# core4.net
KiCad netlist of a schematic drawn in EAGLE
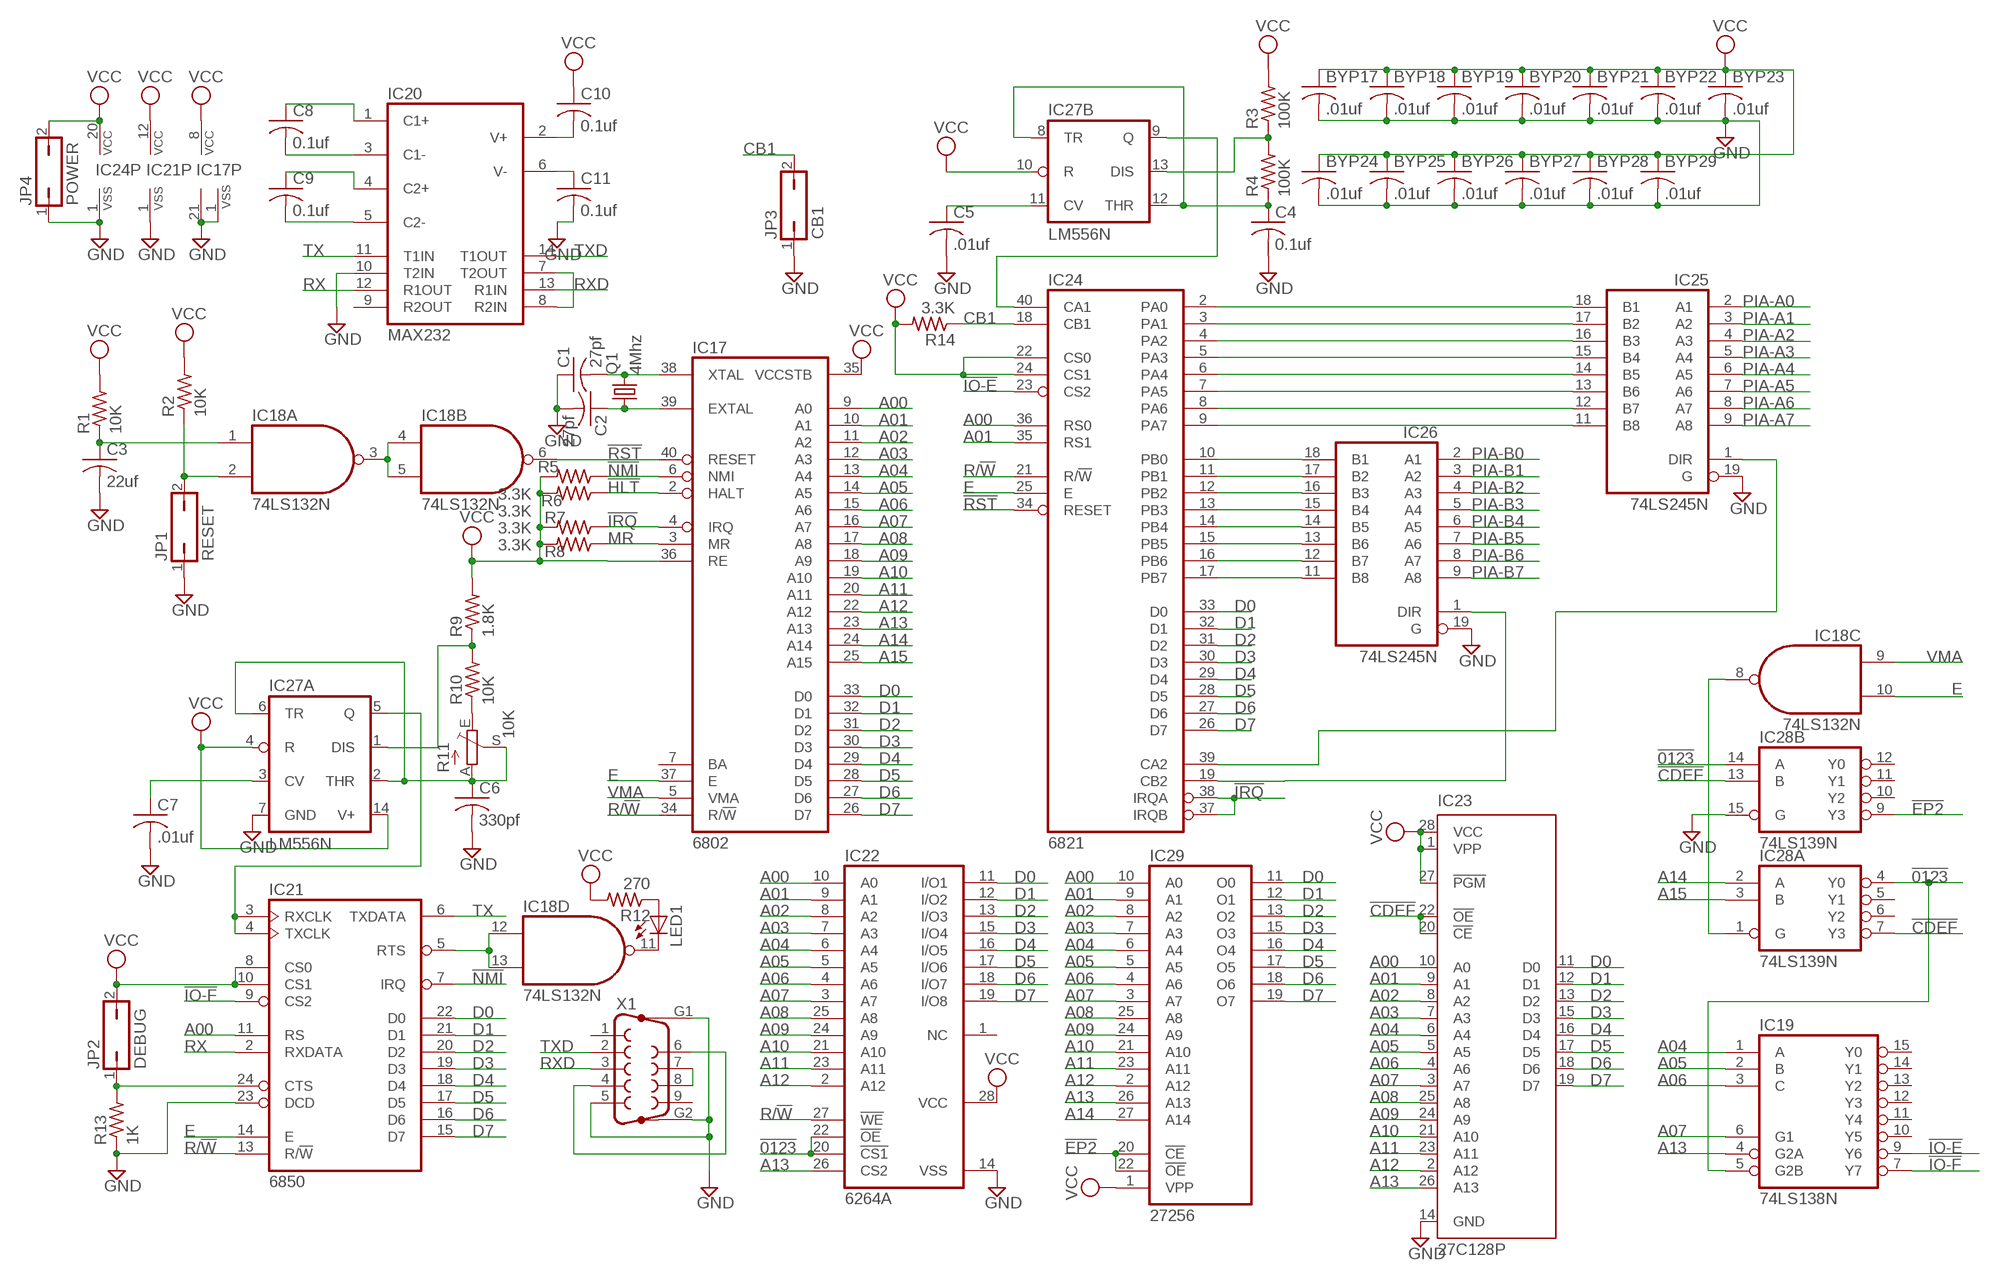
[diagram p0: schematic, sheet 1]
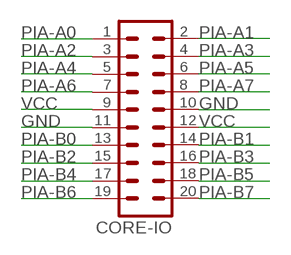
[diagram p1: schematic, sheet 2]

(export (version "E")
  (design (tool "Eeschema 10.0.6"))
  (components
    (comp (ref "CORE-IO")
      (value "MA10-2")
      (footprint "eagle-import:MA10-2")
      (libsource (lib "eagle-import") (part "MA10-2"))
    )
    (comp (ref "BYP17")
      (value ".01uf")
      (footprint "eagle-import:C050-025X075")
      (libsource (lib "eagle-import") (part "C-US050-025X075"))
    )
    (comp (ref "BYP18")
      (value ".01uf")
      (footprint "eagle-import:C050-025X075")
      (libsource (lib "eagle-import") (part "C-US050-025X075"))
    )
    (comp (ref "BYP19")
      (value ".01uf")
      (footprint "eagle-import:C050-025X075")
      (libsource (lib "eagle-import") (part "C-US050-025X075"))
    )
    (comp (ref "BYP20")
      (value ".01uf")
      (footprint "eagle-import:C050-025X075")
      (libsource (lib "eagle-import") (part "C-US050-025X075"))
    )
    (comp (ref "BYP21")
      (value ".01uf")
      (footprint "eagle-import:C050-025X075")
      (libsource (lib "eagle-import") (part "C-US050-025X075"))
    )
    (comp (ref "BYP22")
      (value ".01uf")
      (footprint "eagle-import:C050-025X075")
      (libsource (lib "eagle-import") (part "C-US050-025X075"))
    )
    (comp (ref "BYP23")
      (value ".01uf")
      (footprint "eagle-import:C050-025X075")
      (libsource (lib "eagle-import") (part "C-US050-025X075"))
    )
    (comp (ref "BYP24")
      (value ".01uf")
      (footprint "eagle-import:C050-025X075")
      (libsource (lib "eagle-import") (part "C-US050-025X075"))
    )
    (comp (ref "BYP25")
      (value ".01uf")
      (footprint "eagle-import:C050-025X075")
      (libsource (lib "eagle-import") (part "C-US050-025X075"))
    )
    (comp (ref "BYP26")
      (value ".01uf")
      (footprint "eagle-import:C050-025X075")
      (libsource (lib "eagle-import") (part "C-US050-025X075"))
    )
    (comp (ref "BYP27")
      (value ".01uf")
      (footprint "eagle-import:C050-025X075")
      (libsource (lib "eagle-import") (part "C-US050-025X075"))
    )
    (comp (ref "BYP28")
      (value ".01uf")
      (footprint "eagle-import:C050-025X075")
      (libsource (lib "eagle-import") (part "C-US050-025X075"))
    )
    (comp (ref "BYP29")
      (value ".01uf")
      (footprint "eagle-import:C050-025X075")
      (libsource (lib "eagle-import") (part "C-US050-025X075"))
    )
    (comp (ref "C1")
      (value "27pf")
      (footprint "eagle-import:C050-025X075")
      (libsource (lib "eagle-import") (part "C-US050-025X075"))
    )
    (comp (ref "C2")
      (value "27pf")
      (footprint "eagle-import:C050-025X075")
      (libsource (lib "eagle-import") (part "C-US050-025X075"))
    )
    (comp (ref "C3")
      (value "22uf")
      (footprint "eagle-import:C102-043X133")
      (libsource (lib "eagle-import") (part "C-US102-043X133"))
    )
    (comp (ref "C4")
      (value "0.1uf")
      (footprint "eagle-import:C050-025X075")
      (libsource (lib "eagle-import") (part "C-US050-025X075"))
    )
    (comp (ref "C5")
      (value ".01uf")
      (footprint "eagle-import:C050-025X075")
      (libsource (lib "eagle-import") (part "C-US050-025X075"))
    )
    (comp (ref "C6")
      (value "330pf")
      (footprint "eagle-import:C050-025X075")
      (libsource (lib "eagle-import") (part "C-US050-025X075"))
    )
    (comp (ref "C7")
      (value ".01uf")
      (footprint "eagle-import:C050-025X075")
      (libsource (lib "eagle-import") (part "C-US050-025X075"))
    )
    (comp (ref "C8")
      (value "0.1uf")
      (footprint "eagle-import:C050-025X075")
      (libsource (lib "eagle-import") (part "C-US050-025X075"))
    )
    (comp (ref "C9")
      (value "0.1uf")
      (footprint "eagle-import:C050-025X075")
      (libsource (lib "eagle-import") (part "C-US050-025X075"))
    )
    (comp (ref "C10")
      (value "0.1uf")
      (footprint "eagle-import:C050-025X075")
      (libsource (lib "eagle-import") (part "C-US050-025X075"))
    )
    (comp (ref "C11")
      (value "0.1uf")
      (footprint "eagle-import:C050-025X075")
      (libsource (lib "eagle-import") (part "C-US050-025X075"))
    )
    (comp (ref "IC17")
      (value "6802")
      (footprint "eagle-import:DIL40")
      (libsource (lib "eagle-import") (part "6802"))
    )
    (comp (ref "IC18")
      (value "74LS132N")
      (footprint "eagle-import:DIL14")
      (libsource (lib "eagle-import") (part "7400NLS"))
    )
    (comp (ref "IC19")
      (value "74LS138N")
      (footprint "eagle-import:DIL16")
      (libsource (lib "eagle-import") (part "74138NLS"))
    )
    (comp (ref "IC20")
      (value "MAX232")
      (footprint "eagle-import:DIL16")
      (fields (field (name "MF") "MAXIM") (field (name "MPN") "MAX232ACPE+"))
      (libsource (lib "eagle-import") (part "MAX232"))
    )
    (comp (ref "IC21")
      (value "6850")
      (footprint "eagle-import:DIL24")
      (fields (field (name "MF") "NTE ELECTRONICS") (field (name "MPN") "NTE6850"))
      (libsource (lib "eagle-import") (part "6850"))
    )
    (comp (ref "IC22")
      (value "6264A")
      (footprint "eagle-import:DIL28-6")
      (libsource (lib "eagle-import") (part "6264A"))
    )
    (comp (ref "IC23")
      (value "27C128P")
      (footprint "eagle-import:DIL28-6")
      (libsource (lib "eagle-import") (part "27128PC"))
    )
    (comp (ref "IC24")
      (value "6821")
      (footprint "eagle-import:DIL40")
      (fields (field (name "MF") "NTE ELECTRONICS") (field (name "MPN") "NTE6821"))
      (libsource (lib "eagle-import") (part "6821"))
    )
    (comp (ref "IC25")
      (value "74LS245N")
      (footprint "eagle-import:DIL20")
      (libsource (lib "eagle-import") (part "74245NLS"))
    )
    (comp (ref "IC26")
      (value "74LS245N")
      (footprint "eagle-import:DIL20")
      (libsource (lib "eagle-import") (part "74245NLS"))
    )
    (comp (ref "IC27")
      (value "LM556N")
      (footprint "eagle-import:DIL14")
      (libsource (lib "eagle-import") (part "556NLM"))
    )
    (comp (ref "IC28")
      (value "74LS139N")
      (footprint "eagle-import:DIL16")
      (libsource (lib "eagle-import") (part "74139NLS"))
    )
    (comp (ref "IC29")
      (value "27256")
      (footprint "eagle-import:DIL28")
      (libsource (lib "eagle-import") (part "27256"))
    )
    (comp (ref "JP1")
      (value "RESET")
      (footprint "eagle-import:JP1")
      (libsource (lib "eagle-import") (part "JP1Q"))
    )
    (comp (ref "JP2")
      (value "DEBUG")
      (footprint "eagle-import:JP1")
      (libsource (lib "eagle-import") (part "JP1Q"))
    )
    (comp (ref "JP3")
      (value "CB1")
      (footprint "eagle-import:JP1")
      (libsource (lib "eagle-import") (part "JP1Q"))
    )
    (comp (ref "JP4")
      (value "POWER")
      (footprint "eagle-import:JP1")
      (libsource (lib "eagle-import") (part "JP1Q"))
    )
    (comp (ref "LED1")
      (value "LED3MM")
      (footprint "eagle-import:LED3MM")
      (libsource (lib "eagle-import") (part "LED3MM"))
    )
    (comp (ref "Q1")
      (value "4Mhz")
      (footprint "eagle-import:HC18U-V")
      (libsource (lib "eagle-import") (part "CRYSTALHC18U-V"))
    )
    (comp (ref "R1")
      (value "10K")
      (footprint "eagle-import:0207_7")
      (libsource (lib "eagle-import") (part "R-US_0207/7"))
    )
    (comp (ref "R2")
      (value "10K")
      (footprint "eagle-import:0207_7")
      (libsource (lib "eagle-import") (part "R-US_0207/7"))
    )
    (comp (ref "R3")
      (value "100K")
      (footprint "eagle-import:0207_7")
      (libsource (lib "eagle-import") (part "R-US_0207/7"))
    )
    (comp (ref "R4")
      (value "100K")
      (footprint "eagle-import:0207_7")
      (libsource (lib "eagle-import") (part "R-US_0207/7"))
    )
    (comp (ref "R5")
      (value "3.3K")
      (footprint "eagle-import:0207_7")
      (libsource (lib "eagle-import") (part "R-US_0207/7"))
    )
    (comp (ref "R6")
      (value "3.3K")
      (footprint "eagle-import:0207_7")
      (libsource (lib "eagle-import") (part "R-US_0207/7"))
    )
    (comp (ref "R7")
      (value "3.3K")
      (footprint "eagle-import:0207_7")
      (libsource (lib "eagle-import") (part "R-US_0207/7"))
    )
    (comp (ref "R8")
      (value "3.3K")
      (footprint "eagle-import:0207_7")
      (libsource (lib "eagle-import") (part "R-US_0207/7"))
    )
    (comp (ref "R9")
      (value "1.8K")
      (footprint "eagle-import:0207_7")
      (libsource (lib "eagle-import") (part "R-US_0207/7"))
    )
    (comp (ref "R10")
      (value "10K")
      (footprint "eagle-import:0207_7")
      (libsource (lib "eagle-import") (part "R-US_0207/7"))
    )
    (comp (ref "R11")
      (value "10K")
      (footprint "eagle-import:SP19L")
      (libsource (lib "eagle-import") (part "TRIM_EU-B90P"))
    )
    (comp (ref "R12")
      (value "270")
      (footprint "eagle-import:0207_7")
      (libsource (lib "eagle-import") (part "R-US_0207/7"))
    )
    (comp (ref "R13")
      (value "1K")
      (footprint "eagle-import:0207_7")
      (libsource (lib "eagle-import") (part "R-US_0207/7"))
    )
    (comp (ref "R14")
      (value "3.3K")
      (footprint "eagle-import:0207_7")
      (libsource (lib "eagle-import") (part "R-US_0207/7"))
    )
    (comp (ref "X1")
      (value "F09HP")
      (footprint "eagle-import:F09HP")
      (libsource (lib "eagle-import") (part "F09HP"))
    )
  )
  (nets
    (net (code "1") (name "A00") (class "Default")
      (node (ref "IC17") (pin "9") (pinfunction "A0_9") (pintype "output"))
      (node (ref "IC21") (pin "11") (pinfunction "RS_11") (pintype "input"))
      (node (ref "IC22") (pin "10") (pinfunction "A0_10") (pintype "input"))
      (node (ref "IC23") (pin "10") (pinfunction "A0_10") (pintype "input"))
      (node (ref "IC24") (pin "36") (pinfunction "RS0_36") (pintype "input"))
      (node (ref "IC29") (pin "10") (pinfunction "A0_10") (pintype "input"))
    )
    (net (code "2") (name "A01") (class "Default")
      (node (ref "IC17") (pin "10") (pinfunction "A1_10") (pintype "output"))
      (node (ref "IC22") (pin "9") (pinfunction "A1_9") (pintype "input"))
      (node (ref "IC23") (pin "9") (pinfunction "A1_9") (pintype "input"))
      (node (ref "IC24") (pin "35") (pinfunction "RS1_35") (pintype "input"))
      (node (ref "IC29") (pin "9") (pinfunction "A1_9") (pintype "input"))
    )
    (net (code "3") (name "A02") (class "Default")
      (node (ref "IC17") (pin "11") (pinfunction "A2_11") (pintype "output"))
      (node (ref "IC22") (pin "8") (pinfunction "A2_8") (pintype "input"))
      (node (ref "IC23") (pin "8") (pinfunction "A2_8") (pintype "input"))
      (node (ref "IC29") (pin "8") (pinfunction "A2_8") (pintype "input"))
    )
    (net (code "4") (name "A03") (class "Default")
      (node (ref "IC17") (pin "12") (pinfunction "A3_12") (pintype "output"))
      (node (ref "IC22") (pin "7") (pinfunction "A3_7") (pintype "input"))
      (node (ref "IC23") (pin "7") (pinfunction "A3_7") (pintype "input"))
      (node (ref "IC29") (pin "7") (pinfunction "A3_7") (pintype "input"))
    )
    (net (code "5") (name "A04") (class "Default")
      (node (ref "IC17") (pin "13") (pinfunction "A4_13") (pintype "output"))
      (node (ref "IC19") (pin "1") (pinfunction "A_1") (pintype "input"))
      (node (ref "IC22") (pin "6") (pinfunction "A4_6") (pintype "input"))
      (node (ref "IC23") (pin "6") (pinfunction "A4_6") (pintype "input"))
      (node (ref "IC29") (pin "6") (pinfunction "A4_6") (pintype "input"))
    )
    (net (code "6") (name "A05") (class "Default")
      (node (ref "IC17") (pin "14") (pinfunction "A5_14") (pintype "output"))
      (node (ref "IC19") (pin "2") (pinfunction "B_2") (pintype "input"))
      (node (ref "IC22") (pin "5") (pinfunction "A5_5") (pintype "input"))
      (node (ref "IC23") (pin "5") (pinfunction "A5_5") (pintype "input"))
      (node (ref "IC29") (pin "5") (pinfunction "A5_5") (pintype "input"))
    )
    (net (code "7") (name "A06") (class "Default")
      (node (ref "IC17") (pin "15") (pinfunction "A6_15") (pintype "output"))
      (node (ref "IC19") (pin "3") (pinfunction "C_3") (pintype "input"))
      (node (ref "IC22") (pin "4") (pinfunction "A6_4") (pintype "input"))
      (node (ref "IC23") (pin "4") (pinfunction "A6_4") (pintype "input"))
      (node (ref "IC29") (pin "4") (pinfunction "A6_4") (pintype "input"))
    )
    (net (code "8") (name "A07") (class "Default")
      (node (ref "IC17") (pin "16") (pinfunction "A7_16") (pintype "output"))
      (node (ref "IC19") (pin "6") (pinfunction "G1_6") (pintype "input"))
      (node (ref "IC22") (pin "3") (pinfunction "A7_3") (pintype "input"))
      (node (ref "IC23") (pin "3") (pinfunction "A7_3") (pintype "input"))
      (node (ref "IC29") (pin "3") (pinfunction "A7_3") (pintype "input"))
    )
    (net (code "9") (name "A08") (class "Default")
      (node (ref "IC17") (pin "17") (pinfunction "A8_17") (pintype "output"))
      (node (ref "IC22") (pin "25") (pinfunction "A8_25") (pintype "input"))
      (node (ref "IC23") (pin "25") (pinfunction "A8_25") (pintype "input"))
      (node (ref "IC29") (pin "25") (pinfunction "A8_25") (pintype "input"))
    )
    (net (code "10") (name "A09") (class "Default")
      (node (ref "IC17") (pin "18") (pinfunction "A9_18") (pintype "output"))
      (node (ref "IC22") (pin "24") (pinfunction "A9_24") (pintype "input"))
      (node (ref "IC23") (pin "24") (pinfunction "A9_24") (pintype "input"))
      (node (ref "IC29") (pin "24") (pinfunction "A9_24") (pintype "input"))
    )
    (net (code "11") (name "A10") (class "Default")
      (node (ref "IC17") (pin "19") (pinfunction "A10_19") (pintype "output"))
      (node (ref "IC22") (pin "21") (pinfunction "A10_21") (pintype "input"))
      (node (ref "IC23") (pin "21") (pinfunction "A10_21") (pintype "input"))
      (node (ref "IC29") (pin "21") (pinfunction "A10_21") (pintype "input"))
    )
    (net (code "12") (name "A11") (class "Default")
      (node (ref "IC17") (pin "20") (pinfunction "A11_20") (pintype "output"))
      (node (ref "IC22") (pin "23") (pinfunction "A11_23") (pintype "input"))
      (node (ref "IC23") (pin "23") (pinfunction "A11_23") (pintype "input"))
      (node (ref "IC29") (pin "23") (pinfunction "A11_23") (pintype "input"))
    )
    (net (code "13") (name "A12") (class "Default")
      (node (ref "IC17") (pin "22") (pinfunction "A12_22") (pintype "output"))
      (node (ref "IC22") (pin "2") (pinfunction "A12_2") (pintype "input"))
      (node (ref "IC23") (pin "2") (pinfunction "A12_2") (pintype "input"))
      (node (ref "IC29") (pin "2") (pinfunction "A12_2") (pintype "input"))
    )
    (net (code "14") (name "A13") (class "Default")
      (node (ref "IC17") (pin "23") (pinfunction "A13_23") (pintype "output"))
      (node (ref "IC19") (pin "4") (pinfunction "G2A_4") (pintype "input"))
      (node (ref "IC22") (pin "26") (pinfunction "CS2_26") (pintype "input"))
      (node (ref "IC23") (pin "26") (pinfunction "A13_26") (pintype "input"))
      (node (ref "IC29") (pin "26") (pinfunction "A13_26") (pintype "input"))
    )
    (net (code "15") (name "A14") (class "Default")
      (node (ref "IC17") (pin "24") (pinfunction "A14_24") (pintype "output"))
      (node (ref "IC28") (pin "2") (pinfunction "A_2") (pintype "input"))
      (node (ref "IC29") (pin "27") (pinfunction "A14_27") (pintype "input"))
    )
    (net (code "16") (name "A15") (class "Default")
      (node (ref "IC17") (pin "25") (pinfunction "A15_25") (pintype "output"))
      (node (ref "IC28") (pin "3") (pinfunction "B_3") (pintype "input"))
    )
    (net (code "17") (name "CB1") (class "Default")
      (node (ref "IC24") (pin "18") (pinfunction "CB1_18") (pintype "input"))
      (node (ref "JP3") (pin "2") (pinfunction "2_2") (pintype "passive"))
      (node (ref "R14") (pin "1") (pinfunction "1_1") (pintype "passive"))
    )
    (net (code "18") (name "D0") (class "Default")
      (node (ref "IC17") (pin "33") (pinfunction "D0_33") (pintype "bidirectional"))
      (node (ref "IC21") (pin "22") (pinfunction "D0_22") (pintype "bidirectional"))
      (node (ref "IC22") (pin "11") (pinfunction "I/O1_11") (pintype "bidirectional"))
      (node (ref "IC23") (pin "11") (pinfunction "D0_11") (pintype "tri_state"))
      (node (ref "IC24") (pin "33") (pinfunction "D0_33") (pintype "bidirectional"))
      (node (ref "IC29") (pin "11") (pinfunction "O0_11") (pintype "tri_state"))
    )
    (net (code "19") (name "D1") (class "Default")
      (node (ref "IC17") (pin "32") (pinfunction "D1_32") (pintype "bidirectional"))
      (node (ref "IC21") (pin "21") (pinfunction "D1_21") (pintype "bidirectional"))
      (node (ref "IC22") (pin "12") (pinfunction "I/O2_12") (pintype "bidirectional"))
      (node (ref "IC23") (pin "12") (pinfunction "D1_12") (pintype "tri_state"))
      (node (ref "IC24") (pin "32") (pinfunction "D1_32") (pintype "bidirectional"))
      (node (ref "IC29") (pin "12") (pinfunction "O1_12") (pintype "tri_state"))
    )
    (net (code "20") (name "D2") (class "Default")
      (node (ref "IC17") (pin "31") (pinfunction "D2_31") (pintype "bidirectional"))
      (node (ref "IC21") (pin "20") (pinfunction "D2_20") (pintype "bidirectional"))
      (node (ref "IC22") (pin "13") (pinfunction "I/O3_13") (pintype "bidirectional"))
      (node (ref "IC23") (pin "13") (pinfunction "D2_13") (pintype "tri_state"))
      (node (ref "IC24") (pin "31") (pinfunction "D2_31") (pintype "bidirectional"))
      (node (ref "IC29") (pin "13") (pinfunction "O2_13") (pintype "tri_state"))
    )
    (net (code "21") (name "D3") (class "Default")
      (node (ref "IC17") (pin "30") (pinfunction "D3_30") (pintype "bidirectional"))
      (node (ref "IC21") (pin "19") (pinfunction "D3_19") (pintype "bidirectional"))
      (node (ref "IC22") (pin "15") (pinfunction "I/O4_15") (pintype "bidirectional"))
      (node (ref "IC23") (pin "15") (pinfunction "D3_15") (pintype "tri_state"))
      (node (ref "IC24") (pin "30") (pinfunction "D3_30") (pintype "bidirectional"))
      (node (ref "IC29") (pin "15") (pinfunction "O3_15") (pintype "tri_state"))
    )
    (net (code "22") (name "D4") (class "Default")
      (node (ref "IC17") (pin "29") (pinfunction "D4_29") (pintype "bidirectional"))
      (node (ref "IC21") (pin "18") (pinfunction "D4_18") (pintype "bidirectional"))
      (node (ref "IC22") (pin "16") (pinfunction "I/O5_16") (pintype "bidirectional"))
      (node (ref "IC23") (pin "16") (pinfunction "D4_16") (pintype "tri_state"))
      (node (ref "IC24") (pin "29") (pinfunction "D4_29") (pintype "bidirectional"))
      (node (ref "IC29") (pin "16") (pinfunction "O4_16") (pintype "tri_state"))
    )
    (net (code "23") (name "D5") (class "Default")
      (node (ref "IC17") (pin "28") (pinfunction "D5_28") (pintype "bidirectional"))
      (node (ref "IC21") (pin "17") (pinfunction "D5_17") (pintype "bidirectional"))
      (node (ref "IC22") (pin "17") (pinfunction "I/O6_17") (pintype "bidirectional"))
      (node (ref "IC23") (pin "17") (pinfunction "D5_17") (pintype "tri_state"))
      (node (ref "IC24") (pin "28") (pinfunction "D5_28") (pintype "bidirectional"))
      (node (ref "IC29") (pin "17") (pinfunction "O5_17") (pintype "tri_state"))
    )
    (net (code "24") (name "D6") (class "Default")
      (node (ref "IC17") (pin "27") (pinfunction "D6_27") (pintype "bidirectional"))
      (node (ref "IC21") (pin "16") (pinfunction "D6_16") (pintype "bidirectional"))
      (node (ref "IC22") (pin "18") (pinfunction "I/O7_18") (pintype "bidirectional"))
      (node (ref "IC23") (pin "18") (pinfunction "D6_18") (pintype "tri_state"))
      (node (ref "IC24") (pin "27") (pinfunction "D6_27") (pintype "bidirectional"))
      (node (ref "IC29") (pin "18") (pinfunction "O6_18") (pintype "tri_state"))
    )
    (net (code "25") (name "D7") (class "Default")
      (node (ref "IC17") (pin "26") (pinfunction "D7_26") (pintype "bidirectional"))
      (node (ref "IC21") (pin "15") (pinfunction "D7_15") (pintype "bidirectional"))
      (node (ref "IC22") (pin "19") (pinfunction "I/O8_19") (pintype "bidirectional"))
      (node (ref "IC23") (pin "19") (pinfunction "D7_19") (pintype "tri_state"))
      (node (ref "IC24") (pin "26") (pinfunction "D7_26") (pintype "bidirectional"))
      (node (ref "IC29") (pin "19") (pinfunction "O7_19") (pintype "tri_state"))
    )
    (net (code "26") (name "E") (class "Default")
      (node (ref "IC17") (pin "37") (pinfunction "E_37") (pintype "output"))
      (node (ref "IC18") (pin "10") (pinfunction "I1_10") (pintype "input"))
      (node (ref "IC21") (pin "14") (pinfunction "E_14") (pintype "input"))
      (node (ref "IC24") (pin "25") (pinfunction "E_25") (pintype "input"))
    )
    (net (code "27") (name "GND") (class "Default")
      (node (ref "BYP17") (pin "2") (pinfunction "2_2") (pintype "passive"))
      (node (ref "BYP18") (pin "2") (pinfunction "2_2") (pintype "passive"))
      (node (ref "BYP19") (pin "2") (pinfunction "2_2") (pintype "passive"))
      (node (ref "BYP20") (pin "2") (pinfunction "2_2") (pintype "passive"))
      (node (ref "BYP21") (pin "2") (pinfunction "2_2") (pintype "passive"))
      (node (ref "BYP22") (pin "2") (pinfunction "2_2") (pintype "passive"))
      (node (ref "BYP23") (pin "2") (pinfunction "2_2") (pintype "passive"))
      (node (ref "BYP24") (pin "2") (pinfunction "2_2") (pintype "passive"))
      (node (ref "BYP25") (pin "2") (pinfunction "2_2") (pintype "passive"))
      (node (ref "BYP26") (pin "2") (pinfunction "2_2") (pintype "passive"))
      (node (ref "BYP27") (pin "2") (pinfunction "2_2") (pintype "passive"))
      (node (ref "BYP28") (pin "2") (pinfunction "2_2") (pintype "passive"))
      (node (ref "BYP29") (pin "2") (pinfunction "2_2") (pintype "passive"))
      (node (ref "C1") (pin "1") (pinfunction "1_1") (pintype "passive"))
      (node (ref "C11") (pin "2") (pinfunction "2_2") (pintype "passive"))
      (node (ref "C2") (pin "2") (pinfunction "2_2") (pintype "passive"))
      (node (ref "C3") (pin "2") (pinfunction "2_2") (pintype "passive"))
      (node (ref "C4") (pin "2") (pinfunction "2_2") (pintype "passive"))
      (node (ref "C5") (pin "2") (pinfunction "2_2") (pintype "passive"))
      (node (ref "C6") (pin "2") (pinfunction "2_2") (pintype "passive"))
      (node (ref "C7") (pin "2") (pinfunction "2_2") (pintype "passive"))
      (node (ref "CORE-IO") (pin "10") (pinfunction "10_10") (pintype "passive"))
      (node (ref "CORE-IO") (pin "11") (pinfunction "11_11") (pintype "passive"))
      (node (ref "IC17") (pin "1") (pinfunction "VSS_1") (pintype "power_in"))
      (node (ref "IC17") (pin "21") (pinfunction "VSS_21") (pintype "power_in"))
      (node (ref "IC20") (pin "10") (pinfunction "T2IN_10") (pintype "input"))
      (node (ref "IC21") (pin "1") (pinfunction "VSS_1") (pintype "power_in"))
      (node (ref "IC21") (pin "23") (pinfunction "DCD_23") (pintype "input"))
      (node (ref "IC22") (pin "14") (pinfunction "VSS_14") (pintype "power_in"))
      (node (ref "IC23") (pin "14") (pinfunction "GND_14") (pintype "power_in"))
      (node (ref "IC24") (pin "1") (pinfunction "VSS_1") (pintype "power_in"))
      (node (ref "IC25") (pin "19") (pinfunction "G_19") (pintype "input"))
      (node (ref "IC26") (pin "19") (pinfunction "G_19") (pintype "input"))
      (node (ref "IC27") (pin "7") (pinfunction "GND_7") (pintype "power_in"))
      (node (ref "IC28") (pin "15") (pinfunction "G_15") (pintype "input"))
      (node (ref "JP1") (pin "1") (pinfunction "1_1") (pintype "passive"))
      (node (ref "JP3") (pin "1") (pinfunction "1_1") (pintype "passive"))
      (node (ref "JP4") (pin "1") (pinfunction "1_1") (pintype "passive"))
      (node (ref "R13") (pin "1") (pinfunction "1_1") (pintype "passive"))
      (node (ref "X1") (pin "5") (pinfunction "5_5") (pintype "passive"))
      (node (ref "X1") (pin "G1") (pinfunction "G1_G1") (pintype "passive"))
      (node (ref "X1") (pin "G2") (pinfunction "G2_G2") (pintype "passive"))
    )
    (net (code "28") (name "MR") (class "Default")
      (node (ref "IC17") (pin "3") (pinfunction "MR_3") (pintype "input"))
      (node (ref "R8") (pin "1") (pinfunction "1_1") (pintype "passive"))
    )
    (net (code "29") (name "Net-(IC17A-EXTAL)") (class "Default")
      (node (ref "C2") (pin "1") (pinfunction "1_1") (pintype "passive"))
      (node (ref "IC17") (pin "39") (pinfunction "EXTAL_39") (pintype "input"))
      (node (ref "Q1") (pin "1") (pinfunction "1_1") (pintype "passive"))
    )
    (net (code "30") (name "Net-(IC17A-XTAL)") (class "Default")
      (node (ref "C1") (pin "2") (pinfunction "2_2") (pintype "passive"))
      (node (ref "IC17") (pin "38") (pinfunction "XTAL_38") (pintype "input"))
      (node (ref "Q1") (pin "2") (pinfunction "2_2") (pintype "passive"))
    )
    (net (code "31") (name "Net-(IC18A-I0)") (class "Default")
      (node (ref "C3") (pin "1") (pinfunction "1_1") (pintype "passive"))
      (node (ref "IC18") (pin "1") (pinfunction "I0_1") (pintype "input"))
      (node (ref "R1") (pin "1") (pinfunction "1_1") (pintype "passive"))
    )
    (net (code "32") (name "Net-(IC18A-I1)") (class "Default")
      (node (ref "IC18") (pin "2") (pinfunction "I1_2") (pintype "input"))
      (node (ref "JP1") (pin "2") (pinfunction "2_2") (pintype "passive"))
      (node (ref "R2") (pin "1") (pinfunction "1_1") (pintype "passive"))
    )
    (net (code "33") (name "Net-(IC18A-O)") (class "Default")
      (node (ref "IC18") (pin "3") (pinfunction "O_3") (pintype "output"))
      (node (ref "IC18") (pin "4") (pinfunction "I0_4") (pintype "input"))
      (node (ref "IC18") (pin "5") (pinfunction "I1_5") (pintype "input"))
    )
    (net (code "34") (name "Net-(IC18C-O)") (class "Default")
      (node (ref "IC18") (pin "8") (pinfunction "O_8") (pintype "output"))
      (node (ref "IC28") (pin "1") (pinfunction "G_1") (pintype "input"))
    )
    (net (code "35") (name "Net-(IC18D-I0)") (class "Default")
      (node (ref "IC18") (pin "12") (pinfunction "I0_12") (pintype "input"))
      (node (ref "IC18") (pin "13") (pinfunction "I1_13") (pintype "input"))
      (node (ref "IC21") (pin "5") (pinfunction "RTS_5") (pintype "output"))
    )
    (net (code "36") (name "Net-(IC18D-O)") (class "Default")
      (node (ref "IC18") (pin "11") (pinfunction "O_11") (pintype "output"))
      (node (ref "LED1") (pin "K") (pinfunction "C_K") (pintype "passive"))
    )
    (net (code "37") (name "Net-(IC20A-C1+)") (class "Default")
      (node (ref "C8") (pin "1") (pinfunction "1_1") (pintype "passive"))
      (node (ref "IC20") (pin "1") (pinfunction "C1+_1") (pintype "bidirectional"))
    )
    (net (code "38") (name "Net-(IC20A-C1-)") (class "Default")
      (node (ref "C8") (pin "2") (pinfunction "2_2") (pintype "passive"))
      (node (ref "IC20") (pin "3") (pinfunction "C1-_3") (pintype "bidirectional"))
    )
    (net (code "39") (name "Net-(IC20A-C2+)") (class "Default")
      (node (ref "C9") (pin "1") (pinfunction "1_1") (pintype "passive"))
      (node (ref "IC20") (pin "4") (pinfunction "C2+_4") (pintype "bidirectional"))
    )
    (net (code "40") (name "Net-(IC20A-C2-)") (class "Default")
      (node (ref "C9") (pin "2") (pinfunction "2_2") (pintype "passive"))
      (node (ref "IC20") (pin "5") (pinfunction "C2-_5") (pintype "bidirectional"))
    )
    (net (code "41") (name "Net-(IC20A-R2IN)") (class "Default")
      (node (ref "IC20") (pin "7") (pinfunction "T2OUT_7") (pintype "output"))
      (node (ref "IC20") (pin "8") (pinfunction "R2IN_8") (pintype "input"))
    )
    (net (code "42") (name "Net-(IC20A-V+)") (class "Default")
      (node (ref "C10") (pin "2") (pinfunction "2_2") (pintype "passive"))
      (node (ref "IC20") (pin "2") (pinfunction "V+_2") (pintype "bidirectional"))
    )
    (net (code "43") (name "Net-(IC20A-V-)") (class "Default")
      (node (ref "C11") (pin "1") (pinfunction "1_1") (pintype "passive"))
      (node (ref "IC20") (pin "6") (pinfunction "V-_6") (pintype "bidirectional"))
    )
    (net (code "44") (name "Net-(IC21A-CTS)") (class "Default")
      (node (ref "IC21") (pin "24") (pinfunction "CTS_24") (pintype "input"))
      (node (ref "JP2") (pin "1") (pinfunction "1_1") (pintype "passive"))
      (node (ref "R13") (pin "2") (pinfunction "2_2") (pintype "passive"))
    )
    (net (code "45") (name "Net-(IC21A-RXCLK)") (class "Default")
      (node (ref "IC21") (pin "3") (pinfunction "RXCLK_3") (pintype "input"))
      (node (ref "IC21") (pin "4") (pinfunction "TXCLK_4") (pintype "input"))
      (node (ref "IC27") (pin "5") (pinfunction "Q_5") (pintype "output"))
    )
    (net (code "46") (name "Net-(IC24A-CA1)") (class "Default")
      (node (ref "IC24") (pin "40") (pinfunction "CA1_40") (pintype "input"))
      (node (ref "IC27") (pin "9") (pinfunction "Q_9") (pintype "output"))
    )
    (net (code "47") (name "Net-(IC24A-CA2)") (class "Default")
      (node (ref "IC24") (pin "39") (pinfunction "CA2_39") (pintype "bidirectional"))
      (node (ref "IC25") (pin "1") (pinfunction "DIR_1") (pintype "input"))
    )
    (net (code "48") (name "Net-(IC24A-CB2)") (class "Default")
      (node (ref "IC24") (pin "19") (pinfunction "CB2_19") (pintype "bidirectional"))
      (node (ref "IC26") (pin "1") (pinfunction "DIR_1") (pintype "input"))
    )
    (net (code "49") (name "Net-(IC24A-PA0)") (class "Default")
      (node (ref "IC24") (pin "2") (pinfunction "PA0_2") (pintype "bidirectional"))
      (node (ref "IC25") (pin "18") (pinfunction "B1_18") (pintype "bidirectional"))
    )
    (net (code "50") (name "Net-(IC24A-PA1)") (class "Default")
      (node (ref "IC24") (pin "3") (pinfunction "PA1_3") (pintype "bidirectional"))
      (node (ref "IC25") (pin "17") (pinfunction "B2_17") (pintype "bidirectional"))
    )
    (net (code "51") (name "Net-(IC24A-PA2)") (class "Default")
      (node (ref "IC24") (pin "4") (pinfunction "PA2_4") (pintype "bidirectional"))
      (node (ref "IC25") (pin "16") (pinfunction "B3_16") (pintype "bidirectional"))
    )
    (net (code "52") (name "Net-(IC24A-PA3)") (class "Default")
      (node (ref "IC24") (pin "5") (pinfunction "PA3_5") (pintype "bidirectional"))
      (node (ref "IC25") (pin "15") (pinfunction "B4_15") (pintype "bidirectional"))
    )
    (net (code "53") (name "Net-(IC24A-PA4)") (class "Default")
      (node (ref "IC24") (pin "6") (pinfunction "PA4_6") (pintype "bidirectional"))
      (node (ref "IC25") (pin "14") (pinfunction "B5_14") (pintype "bidirectional"))
    )
    (net (code "54") (name "Net-(IC24A-PA5)") (class "Default")
      (node (ref "IC24") (pin "7") (pinfunction "PA5_7") (pintype "bidirectional"))
      (node (ref "IC25") (pin "13") (pinfunction "B6_13") (pintype "bidirectional"))
    )
    (net (code "55") (name "Net-(IC24A-PA6)") (class "Default")
      (node (ref "IC24") (pin "8") (pinfunction "PA6_8") (pintype "bidirectional"))
      (node (ref "IC25") (pin "12") (pinfunction "B7_12") (pintype "bidirectional"))
    )
    (net (code "56") (name "Net-(IC24A-PA7)") (class "Default")
      (node (ref "IC24") (pin "9") (pinfunction "PA7_9") (pintype "bidirectional"))
      (node (ref "IC25") (pin "11") (pinfunction "B8_11") (pintype "bidirectional"))
    )
    (net (code "57") (name "Net-(IC24A-PB0)") (class "Default")
      (node (ref "IC24") (pin "10") (pinfunction "PB0_10") (pintype "bidirectional"))
      (node (ref "IC26") (pin "18") (pinfunction "B1_18") (pintype "bidirectional"))
    )
    (net (code "58") (name "Net-(IC24A-PB1)") (class "Default")
      (node (ref "IC24") (pin "11") (pinfunction "PB1_11") (pintype "bidirectional"))
      (node (ref "IC26") (pin "17") (pinfunction "B2_17") (pintype "bidirectional"))
    )
    (net (code "59") (name "Net-(IC24A-PB2)") (class "Default")
      (node (ref "IC24") (pin "12") (pinfunction "PB2_12") (pintype "bidirectional"))
      (node (ref "IC26") (pin "16") (pinfunction "B3_16") (pintype "bidirectional"))
    )
    (net (code "60") (name "Net-(IC24A-PB3)") (class "Default")
      (node (ref "IC24") (pin "13") (pinfunction "PB3_13") (pintype "bidirectional"))
      (node (ref "IC26") (pin "15") (pinfunction "B4_15") (pintype "bidirectional"))
    )
    (net (code "61") (name "Net-(IC24A-PB4)") (class "Default")
      (node (ref "IC24") (pin "14") (pinfunction "PB4_14") (pintype "bidirectional"))
      (node (ref "IC26") (pin "14") (pinfunction "B5_14") (pintype "bidirectional"))
    )
    (net (code "62") (name "Net-(IC24A-PB5)") (class "Default")
      (node (ref "IC24") (pin "15") (pinfunction "PB5_15") (pintype "bidirectional"))
      (node (ref "IC26") (pin "13") (pinfunction "B6_13") (pintype "bidirectional"))
    )
    (net (code "63") (name "Net-(IC24A-PB6)") (class "Default")
      (node (ref "IC24") (pin "16") (pinfunction "PB6_16") (pintype "bidirectional"))
      (node (ref "IC26") (pin "12") (pinfunction "B7_12") (pintype "bidirectional"))
    )
    (net (code "64") (name "Net-(IC24A-PB7)") (class "Default")
      (node (ref "IC24") (pin "17") (pinfunction "PB7_17") (pintype "bidirectional"))
      (node (ref "IC26") (pin "11") (pinfunction "B8_11") (pintype "bidirectional"))
    )
    (net (code "65") (name "Net-(IC27A-CV)") (class "Default")
      (node (ref "C7") (pin "1") (pinfunction "1_1") (pintype "passive"))
      (node (ref "IC27") (pin "3") (pinfunction "CV_3") (pintype "input"))
    )
    (net (code "66") (name "Net-(IC27A-DIS)") (class "Default")
      (node (ref "IC27") (pin "1") (pinfunction "DIS_1") (pintype "input"))
      (node (ref "R10") (pin "2") (pinfunction "2_2") (pintype "passive"))
      (node (ref "R9") (pin "1") (pinfunction "1_1") (pintype "passive"))
    )
    (net (code "67") (name "Net-(IC27A-THR)") (class "Default")
      (node (ref "C6") (pin "1") (pinfunction "1_1") (pintype "passive"))
      (node (ref "IC27") (pin "2") (pinfunction "THR_2") (pintype "input"))
      (node (ref "IC27") (pin "6") (pinfunction "TR_6") (pintype "input"))
      (node (ref "R11") (pin "A") (pinfunction "A_A") (pintype "passive"))
      (node (ref "R11") (pin "S") (pinfunction "S_S") (pintype "passive"))
    )
    (net (code "68") (name "Net-(IC27B-CV)") (class "Default")
      (node (ref "C5") (pin "1") (pinfunction "1_1") (pintype "passive"))
      (node (ref "IC27") (pin "11") (pinfunction "CV_11") (pintype "input"))
    )
    (net (code "69") (name "Net-(IC27B-DIS)") (class "Default")
      (node (ref "IC27") (pin "13") (pinfunction "DIS_13") (pintype "input"))
      (node (ref "R3") (pin "1") (pinfunction "1_1") (pintype "passive"))
      (node (ref "R4") (pin "2") (pinfunction "2_2") (pintype "passive"))
    )
    (net (code "70") (name "Net-(IC27B-THR)") (class "Default")
      (node (ref "C4") (pin "1") (pinfunction "1_1") (pintype "passive"))
      (node (ref "IC27") (pin "12") (pinfunction "THR_12") (pintype "input"))
      (node (ref "IC27") (pin "8") (pinfunction "TR_8") (pintype "input"))
      (node (ref "R4") (pin "1") (pinfunction "1_1") (pintype "passive"))
    )
    (net (code "71") (name "Net-(LED1-PadA)") (class "Default")
      (node (ref "LED1") (pin "A") (pinfunction "A_A") (pintype "passive"))
      (node (ref "R12") (pin "1") (pinfunction "1_1") (pintype "passive"))
    )
    (net (code "72") (name "Net-(R10-Pad1)") (class "Default")
      (node (ref "R10") (pin "1") (pinfunction "1_1") (pintype "passive"))
      (node (ref "R11") (pin "E") (pinfunction "E_E") (pintype "passive"))
    )
    (net (code "73") (name "Net-(X1-Pad4)") (class "Default")
      (node (ref "X1") (pin "4") (pinfunction "4_4") (pintype "passive"))
      (node (ref "X1") (pin "6") (pinfunction "6_6") (pintype "passive"))
    )
    (net (code "74") (name "Net-(X1-Pad7)") (class "Default")
      (node (ref "X1") (pin "7") (pinfunction "7_7") (pintype "passive"))
      (node (ref "X1") (pin "8") (pinfunction "8_8") (pintype "passive"))
    )
    (net (code "75") (name "PIA-A0") (class "Default")
      (node (ref "CORE-IO") (pin "1") (pinfunction "1_1") (pintype "passive"))
      (node (ref "IC25") (pin "2") (pinfunction "A1_2") (pintype "bidirectional"))
    )
    (net (code "76") (name "PIA-A1") (class "Default")
      (node (ref "CORE-IO") (pin "2") (pinfunction "2_2") (pintype "passive"))
      (node (ref "IC25") (pin "3") (pinfunction "A2_3") (pintype "bidirectional"))
    )
    (net (code "77") (name "PIA-A2") (class "Default")
      (node (ref "CORE-IO") (pin "3") (pinfunction "3_3") (pintype "passive"))
      (node (ref "IC25") (pin "4") (pinfunction "A3_4") (pintype "bidirectional"))
    )
    (net (code "78") (name "PIA-A3") (class "Default")
      (node (ref "CORE-IO") (pin "4") (pinfunction "4_4") (pintype "passive"))
      (node (ref "IC25") (pin "5") (pinfunction "A4_5") (pintype "bidirectional"))
    )
    (net (code "79") (name "PIA-A4") (class "Default")
      (node (ref "CORE-IO") (pin "5") (pinfunction "5_5") (pintype "passive"))
      (node (ref "IC25") (pin "6") (pinfunction "A5_6") (pintype "bidirectional"))
    )
    (net (code "80") (name "PIA-A5") (class "Default")
      (node (ref "CORE-IO") (pin "6") (pinfunction "6_6") (pintype "passive"))
      (node (ref "IC25") (pin "7") (pinfunction "A6_7") (pintype "bidirectional"))
    )
    (net (code "81") (name "PIA-A6") (class "Default")
      (node (ref "CORE-IO") (pin "7") (pinfunction "7_7") (pintype "passive"))
      (node (ref "IC25") (pin "8") (pinfunction "A7_8") (pintype "bidirectional"))
    )
    (net (code "82") (name "PIA-A7") (class "Default")
      (node (ref "CORE-IO") (pin "8") (pinfunction "8_8") (pintype "passive"))
      (node (ref "IC25") (pin "9") (pinfunction "A8_9") (pintype "bidirectional"))
    )
    (net (code "83") (name "PIA-B0") (class "Default")
      (node (ref "CORE-IO") (pin "13") (pinfunction "13_13") (pintype "passive"))
      (node (ref "IC26") (pin "2") (pinfunction "A1_2") (pintype "bidirectional"))
    )
    (net (code "84") (name "PIA-B1") (class "Default")
      (node (ref "CORE-IO") (pin "14") (pinfunction "14_14") (pintype "passive"))
      (node (ref "IC26") (pin "3") (pinfunction "A2_3") (pintype "bidirectional"))
    )
    (net (code "85") (name "PIA-B2") (class "Default")
      (node (ref "CORE-IO") (pin "15") (pinfunction "15_15") (pintype "passive"))
      (node (ref "IC26") (pin "4") (pinfunction "A3_4") (pintype "bidirectional"))
    )
    (net (code "86") (name "PIA-B3") (class "Default")
      (node (ref "CORE-IO") (pin "16") (pinfunction "16_16") (pintype "passive"))
      (node (ref "IC26") (pin "5") (pinfunction "A4_5") (pintype "bidirectional"))
    )
    (net (code "87") (name "PIA-B4") (class "Default")
      (node (ref "CORE-IO") (pin "17") (pinfunction "17_17") (pintype "passive"))
      (node (ref "IC26") (pin "6") (pinfunction "A5_6") (pintype "bidirectional"))
    )
    (net (code "88") (name "PIA-B5") (class "Default")
      (node (ref "CORE-IO") (pin "18") (pinfunction "18_18") (pintype "passive"))
      (node (ref "IC26") (pin "7") (pinfunction "A6_7") (pintype "bidirectional"))
    )
    (net (code "89") (name "PIA-B6") (class "Default")
      (node (ref "CORE-IO") (pin "19") (pinfunction "19_19") (pintype "passive"))
      (node (ref "IC26") (pin "8") (pinfunction "A7_8") (pintype "bidirectional"))
    )
    (net (code "90") (name "PIA-B7") (class "Default")
      (node (ref "CORE-IO") (pin "20") (pinfunction "20_20") (pintype "passive"))
      (node (ref "IC26") (pin "9") (pinfunction "A8_9") (pintype "bidirectional"))
    )
    (net (code "91") (name "RX") (class "Default")
      (node (ref "IC20") (pin "12") (pinfunction "R1OUT_12") (pintype "output"))
      (node (ref "IC21") (pin "2") (pinfunction "RXDATA_2") (pintype "input"))
    )
    (net (code "92") (name "RXD") (class "Default")
      (node (ref "IC20") (pin "13") (pinfunction "R1IN_13") (pintype "input"))
      (node (ref "X1") (pin "3") (pinfunction "3_3") (pintype "passive"))
    )
    (net (code "93") (name "R{slash}~{W}") (class "Default")
      (node (ref "IC17") (pin "34") (pinfunction "R/~{W}_34") (pintype "output"))
      (node (ref "IC21") (pin "13") (pinfunction "R/~{W}_13") (pintype "input"))
      (node (ref "IC22") (pin "27") (pinfunction "~{WE}_27") (pintype "input"))
      (node (ref "IC24") (pin "21") (pinfunction "R/~{W}_21") (pintype "input"))
    )
    (net (code "94") (name "TX") (class "Default")
      (node (ref "IC20") (pin "11") (pinfunction "T1IN_11") (pintype "input"))
      (node (ref "IC21") (pin "6") (pinfunction "TXDATA_6") (pintype "output"))
    )
    (net (code "95") (name "TXD") (class "Default")
      (node (ref "IC20") (pin "14") (pinfunction "T1OUT_14") (pintype "output"))
      (node (ref "X1") (pin "2") (pinfunction "2_2") (pintype "passive"))
    )
    (net (code "96") (name "VCC") (class "Default")
      (node (ref "BYP17") (pin "1") (pinfunction "1_1") (pintype "passive"))
      (node (ref "BYP18") (pin "1") (pinfunction "1_1") (pintype "passive"))
      (node (ref "BYP19") (pin "1") (pinfunction "1_1") (pintype "passive"))
      (node (ref "BYP20") (pin "1") (pinfunction "1_1") (pintype "passive"))
      (node (ref "BYP21") (pin "1") (pinfunction "1_1") (pintype "passive"))
      (node (ref "BYP22") (pin "1") (pinfunction "1_1") (pintype "passive"))
      (node (ref "BYP23") (pin "1") (pinfunction "1_1") (pintype "passive"))
      (node (ref "BYP24") (pin "1") (pinfunction "1_1") (pintype "passive"))
      (node (ref "BYP25") (pin "1") (pinfunction "1_1") (pintype "passive"))
      (node (ref "BYP26") (pin "1") (pinfunction "1_1") (pintype "passive"))
      (node (ref "BYP27") (pin "1") (pinfunction "1_1") (pintype "passive"))
      (node (ref "BYP28") (pin "1") (pinfunction "1_1") (pintype "passive"))
      (node (ref "BYP29") (pin "1") (pinfunction "1_1") (pintype "passive"))
      (node (ref "C10") (pin "1") (pinfunction "1_1") (pintype "passive"))
      (node (ref "CORE-IO") (pin "12") (pinfunction "12_12") (pintype "passive"))
      (node (ref "CORE-IO") (pin "9") (pinfunction "9_9") (pintype "passive"))
      (node (ref "IC17") (pin "35") (pinfunction "VCCSTB_35") (pintype "input"))
      (node (ref "IC17") (pin "36") (pinfunction "RE_36") (pintype "input"))
      (node (ref "IC17") (pin "8") (pinfunction "VCC_8") (pintype "power_in"))
      (node (ref "IC21") (pin "10") (pinfunction "CS1_10") (pintype "input"))
      (node (ref "IC21") (pin "12") (pinfunction "VCC_12") (pintype "power_in"))
      (node (ref "IC21") (pin "8") (pinfunction "CS0_8") (pintype "input"))
      (node (ref "IC22") (pin "28") (pinfunction "VCC_28") (pintype "power_in"))
      (node (ref "IC23") (pin "1") (pinfunction "VPP_1") (pintype "input"))
      (node (ref "IC23") (pin "27") (pinfunction "~{PGM}_27") (pintype "passive"))
      (node (ref "IC23") (pin "28") (pinfunction "VCC_28") (pintype "power_in"))
      (node (ref "IC24") (pin "20") (pinfunction "VCC_20") (pintype "power_in"))
      (node (ref "IC24") (pin "22") (pinfunction "CS0_22") (pintype "input"))
      (node (ref "IC24") (pin "24") (pinfunction "CS1_24") (pintype "input"))
      (node (ref "IC27") (pin "10") (pinfunction "R_10") (pintype "input"))
      (node (ref "IC27") (pin "14") (pinfunction "V+_14") (pintype "power_in"))
      (node (ref "IC27") (pin "4") (pinfunction "R_4") (pintype "input"))
      (node (ref "IC29") (pin "1") (pinfunction "VPP_1") (pintype "input"))
      (node (ref "JP2") (pin "2") (pinfunction "2_2") (pintype "passive"))
      (node (ref "JP4") (pin "2") (pinfunction "2_2") (pintype "passive"))
      (node (ref "R1") (pin "2") (pinfunction "2_2") (pintype "passive"))
      (node (ref "R12") (pin "2") (pinfunction "2_2") (pintype "passive"))
      (node (ref "R14") (pin "2") (pinfunction "2_2") (pintype "passive"))
      (node (ref "R2") (pin "2") (pinfunction "2_2") (pintype "passive"))
      (node (ref "R3") (pin "2") (pinfunction "2_2") (pintype "passive"))
      (node (ref "R5") (pin "2") (pinfunction "2_2") (pintype "passive"))
      (node (ref "R6") (pin "2") (pinfunction "2_2") (pintype "passive"))
      (node (ref "R7") (pin "2") (pinfunction "2_2") (pintype "passive"))
      (node (ref "R8") (pin "2") (pinfunction "2_2") (pintype "passive"))
      (node (ref "R9") (pin "2") (pinfunction "2_2") (pintype "passive"))
    )
    (net (code "97") (name "VMA") (class "Default")
      (node (ref "IC17") (pin "5") (pinfunction "VMA_5") (pintype "output"))
      (node (ref "IC18") (pin "9") (pinfunction "I0_9") (pintype "input"))
    )
    (net (code "98") (name "unconnected-(IC17A-BA-Pad7)") (class "Default")
      (node (ref "IC17") (pin "7") (pinfunction "BA_7") (pintype "output"))
    )
    (net (code "99") (name "unconnected-(IC19A-Y0-Pad15)") (class "Default")
      (node (ref "IC19") (pin "15") (pinfunction "Y0_15") (pintype "output"))
    )
    (net (code "100") (name "unconnected-(IC19A-Y1-Pad14)") (class "Default")
      (node (ref "IC19") (pin "14") (pinfunction "Y1_14") (pintype "output"))
    )
    (net (code "101") (name "unconnected-(IC19A-Y2-Pad13)") (class "Default")
      (node (ref "IC19") (pin "13") (pinfunction "Y2_13") (pintype "output"))
    )
    (net (code "102") (name "unconnected-(IC19A-Y3-Pad12)") (class "Default")
      (node (ref "IC19") (pin "12") (pinfunction "Y3_12") (pintype "output"))
    )
    (net (code "103") (name "unconnected-(IC19A-Y4-Pad11)") (class "Default")
      (node (ref "IC19") (pin "11") (pinfunction "Y4_11") (pintype "output"))
    )
    (net (code "104") (name "unconnected-(IC19A-Y5-Pad10)") (class "Default")
      (node (ref "IC19") (pin "10") (pinfunction "Y5_10") (pintype "output"))
    )
    (net (code "105") (name "unconnected-(IC20A-R2OUT-Pad9)") (class "Default")
      (node (ref "IC20") (pin "9") (pinfunction "R2OUT_9") (pintype "output"))
    )
    (net (code "106") (name "unconnected-(IC22-NC-Pad1)") (class "Default")
      (node (ref "IC22") (pin "1") (pinfunction "NC_1") (pintype "no_connect"))
    )
    (net (code "107") (name "unconnected-(IC28A-Y1-Pad5)") (class "Default")
      (node (ref "IC28") (pin "5") (pinfunction "Y1_5") (pintype "output"))
    )
    (net (code "108") (name "unconnected-(IC28A-Y2-Pad6)") (class "Default")
      (node (ref "IC28") (pin "6") (pinfunction "Y2_6") (pintype "output"))
    )
    (net (code "109") (name "unconnected-(IC28B-Y0-Pad12)") (class "Default")
      (node (ref "IC28") (pin "12") (pinfunction "Y0_12") (pintype "output"))
    )
    (net (code "110") (name "unconnected-(IC28B-Y1-Pad11)") (class "Default")
      (node (ref "IC28") (pin "11") (pinfunction "Y1_11") (pintype "output"))
    )
    (net (code "111") (name "unconnected-(IC28B-Y2-Pad10)") (class "Default")
      (node (ref "IC28") (pin "10") (pinfunction "Y2_10") (pintype "output"))
    )
    (net (code "112") (name "unconnected-(X1-Pad1)") (class "Default")
      (node (ref "X1") (pin "1") (pinfunction "1_1") (pintype "passive"))
    )
    (net (code "113") (name "unconnected-(X1-Pad9)") (class "Default")
      (node (ref "X1") (pin "9") (pinfunction "9_9") (pintype "passive"))
    )
    (net (code "114") (name "~{0123}") (class "Default")
      (node (ref "IC19") (pin "5") (pinfunction "G2B_5") (pintype "input"))
      (node (ref "IC22") (pin "20") (pinfunction "~{CS1}_20") (pintype "input"))
      (node (ref "IC22") (pin "22") (pinfunction "~{OE}_22") (pintype "input"))
      (node (ref "IC28") (pin "14") (pinfunction "A_14") (pintype "input"))
      (node (ref "IC28") (pin "4") (pinfunction "Y0_4") (pintype "output"))
    )
    (net (code "115") (name "~{CDEF}") (class "Default")
      (node (ref "IC23") (pin "20") (pinfunction "~{CE}_20") (pintype "input"))
      (node (ref "IC23") (pin "22") (pinfunction "~{OE}_22") (pintype "input"))
      (node (ref "IC28") (pin "13") (pinfunction "B_13") (pintype "input"))
      (node (ref "IC28") (pin "7") (pinfunction "Y3_7") (pintype "output"))
    )
    (net (code "116") (name "~{EP2}") (class "Default")
      (node (ref "IC28") (pin "9") (pinfunction "Y3_9") (pintype "output"))
      (node (ref "IC29") (pin "20") (pinfunction "~{CE}_20") (pintype "input"))
      (node (ref "IC29") (pin "22") (pinfunction "~{OE}_22") (pintype "input"))
    )
    (net (code "117") (name "~{HLT}") (class "Default")
      (node (ref "IC17") (pin "2") (pinfunction "HALT_2") (pintype "input"))
      (node (ref "R5") (pin "1") (pinfunction "1_1") (pintype "passive"))
    )
    (net (code "118") (name "~{IO-E}") (class "Default")
      (node (ref "IC19") (pin "9") (pinfunction "Y6_9") (pintype "output"))
      (node (ref "IC24") (pin "23") (pinfunction "CS2_23") (pintype "input"))
    )
    (net (code "119") (name "~{IO-F}") (class "Default")
      (node (ref "IC19") (pin "7") (pinfunction "Y7_7") (pintype "output"))
      (node (ref "IC21") (pin "9") (pinfunction "CS2_9") (pintype "input"))
    )
    (net (code "120") (name "~{IRQ}") (class "Default")
      (node (ref "IC17") (pin "4") (pinfunction "IRQ_4") (pintype "input"))
      (node (ref "IC24") (pin "37") (pinfunction "IRQB_37") (pintype "open_collector"))
      (node (ref "IC24") (pin "38") (pinfunction "IRQA_38") (pintype "open_collector"))
      (node (ref "R7") (pin "1") (pinfunction "1_1") (pintype "passive"))
    )
    (net (code "121") (name "~{NMI}") (class "Default")
      (node (ref "IC17") (pin "6") (pinfunction "NMI_6") (pintype "input"))
      (node (ref "IC21") (pin "7") (pinfunction "IRQ_7") (pintype "output"))
      (node (ref "R6") (pin "1") (pinfunction "1_1") (pintype "passive"))
    )
    (net (code "122") (name "~{RST}") (class "Default")
      (node (ref "IC17") (pin "40") (pinfunction "RESET_40") (pintype "input"))
      (node (ref "IC18") (pin "6") (pinfunction "O_6") (pintype "output"))
      (node (ref "IC24") (pin "34") (pinfunction "RESET_34") (pintype "input"))
    )
  )
)
